# schematic.net
KiCad netlist of a schematic drawn in EAGLE
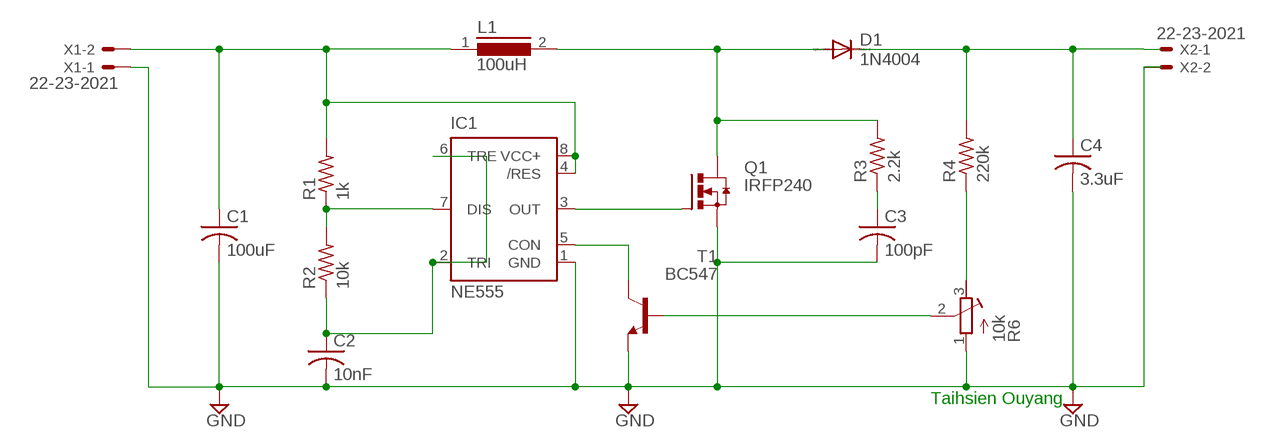
[diagram p0: schematic, sheet 1]

(export (version "E")
  (design (tool "Eeschema 10.0.6"))
  (components
    (comp (ref "C1")
      (value "100uF")
      (footprint "eagle-import:C050-025X075")
      (libsource (lib "eagle-import") (part "C-US050-025X075"))
    )
    (comp (ref "C2")
      (value "10nF")
      (footprint "eagle-import:C050-025X075")
      (libsource (lib "eagle-import") (part "C-US050-025X075"))
    )
    (comp (ref "C3")
      (value "100pF")
      (footprint "eagle-import:C050-025X075")
      (libsource (lib "eagle-import") (part "C-US050-025X075"))
    )
    (comp (ref "C4")
      (value "3.3uF")
      (footprint "eagle-import:C050-025X075")
      (libsource (lib "eagle-import") (part "C-US050-025X075"))
    )
    (comp (ref "D1")
      (value "1N4004")
      (footprint "eagle-import:DO41-10")
      (libsource (lib "eagle-import") (part "1N4004"))
    )
    (comp (ref "IC1")
      (value "NE555")
      (footprint "eagle-import:DIL-08")
      (fields (field (name "MF") "Arrow Electronics") (field (name "MPN") "NE555N"))
      (libsource (lib "eagle-import") (part "NE555"))
    )
    (comp (ref "L1")
      (value "100uH")
      (footprint "eagle-import:SFT1040")
      (libsource (lib "eagle-import") (part "SFT1040"))
    )
    (comp (ref "Q1")
      (value "IRFP240")
      (footprint "eagle-import:TO247BV")
      (libsource (lib "eagle-import") (part "IRFP240"))
    )
    (comp (ref "R1")
      (value "1k")
      (footprint "eagle-import:0207_7")
      (libsource (lib "eagle-import") (part "R-US_0207/7"))
    )
    (comp (ref "R2")
      (value "10k")
      (footprint "eagle-import:0207_7")
      (libsource (lib "eagle-import") (part "R-US_0207/7"))
    )
    (comp (ref "R3")
      (value "2.2k")
      (footprint "eagle-import:0207_7")
      (libsource (lib "eagle-import") (part "R-US_0207/7"))
    )
    (comp (ref "R4")
      (value "220k")
      (footprint "eagle-import:0207_7")
      (libsource (lib "eagle-import") (part "R-US_0207/7"))
    )
    (comp (ref "R6")
      (value "10k")
      (footprint "eagle-import:RTRIM3339P")
      (libsource (lib "eagle-import") (part "R-TRIMM3339P"))
    )
    (comp (ref "T1")
      (value "BC547")
      (footprint "eagle-import:TO92")
      (libsource (lib "eagle-import") (part "BC547"))
    )
    (comp (ref "X1")
      (value "22-23-2021")
      (footprint "eagle-import:22-23-2021")
      (fields (field (name "MF") "MOLEX"))
      (libsource (lib "eagle-import") (part "22-23-2021"))
    )
    (comp (ref "X2")
      (value "22-23-2021")
      (footprint "eagle-import:22-23-2021")
      (fields (field (name "MF") "MOLEX"))
      (libsource (lib "eagle-import") (part "22-23-2021"))
    )
  )
  (nets
    (net (code "1") (name "GND") (class "Default")
      (node (ref "C1") (pin "2") (pinfunction "2_2") (pintype "passive"))
      (node (ref "C2") (pin "2") (pinfunction "2_2") (pintype "passive"))
      (node (ref "C3") (pin "2") (pinfunction "2_2") (pintype "passive"))
      (node (ref "C4") (pin "2") (pinfunction "2_2") (pintype "passive"))
      (node (ref "IC1") (pin "1") (pinfunction "GND_1") (pintype "power_in"))
      (node (ref "Q1") (pin "S") (pinfunction "S_S") (pintype "passive"))
      (node (ref "R6") (pin "1") (pinfunction "A_1") (pintype "passive"))
      (node (ref "T1") (pin "1") (pinfunction "E_1") (pintype "passive"))
      (node (ref "X1") (pin "1") (pinfunction "S_1") (pintype "passive"))
      (node (ref "X2") (pin "2") (pinfunction "S_2") (pintype "passive"))
    )
    (net (code "2") (name "Net-(C3-Pad1)") (class "Default")
      (node (ref "C3") (pin "1") (pinfunction "1_1") (pintype "passive"))
      (node (ref "R3") (pin "1") (pinfunction "1_1") (pintype "passive"))
    )
    (net (code "3") (name "Net-(D1-PadA)") (class "Default")
      (node (ref "D1") (pin "A") (pinfunction "A_A") (pintype "passive"))
      (node (ref "L1") (pin "2") (pinfunction "2_2") (pintype "passive"))
      (node (ref "Q1") (pin "D") (pinfunction "D_D") (pintype "passive"))
      (node (ref "R3") (pin "2") (pinfunction "2_2") (pintype "passive"))
    )
    (net (code "4") (name "Net-(IC1-CON)") (class "Default")
      (node (ref "IC1") (pin "5") (pinfunction "CON_5") (pintype "input"))
      (node (ref "T1") (pin "3") (pinfunction "C_3") (pintype "passive"))
    )
    (net (code "5") (name "Net-(IC1-DIS)") (class "Default")
      (node (ref "IC1") (pin "7") (pinfunction "DIS_7") (pintype "input"))
      (node (ref "R1") (pin "1") (pinfunction "1_1") (pintype "passive"))
      (node (ref "R2") (pin "2") (pinfunction "2_2") (pintype "passive"))
    )
    (net (code "6") (name "Net-(IC1-OUT)") (class "Default")
      (node (ref "IC1") (pin "3") (pinfunction "OUT_3") (pintype "output"))
      (node (ref "Q1") (pin "G") (pinfunction "G_G") (pintype "passive"))
    )
    (net (code "7") (name "Net-(IC1-TRE)") (class "Default")
      (node (ref "C2") (pin "1") (pinfunction "1_1") (pintype "passive"))
      (node (ref "IC1") (pin "2") (pinfunction "TRI_2") (pintype "input"))
      (node (ref "IC1") (pin "6") (pinfunction "TRE_6") (pintype "input"))
      (node (ref "R2") (pin "1") (pinfunction "1_1") (pintype "passive"))
    )
    (net (code "8") (name "Net-(IC1-VCC+)") (class "Default")
      (node (ref "C1") (pin "1") (pinfunction "1_1") (pintype "passive"))
      (node (ref "IC1") (pin "4") (pinfunction "/RES_4") (pintype "input"))
      (node (ref "IC1") (pin "8") (pinfunction "VCC+_8") (pintype "power_in"))
      (node (ref "L1") (pin "1") (pinfunction "1_1") (pintype "passive"))
      (node (ref "R1") (pin "2") (pinfunction "2_2") (pintype "passive"))
      (node (ref "X1") (pin "2") (pinfunction "S_2") (pintype "passive"))
    )
    (net (code "9") (name "Net-(R6-E)") (class "Default")
      (node (ref "R4") (pin "1") (pinfunction "1_1") (pintype "passive"))
      (node (ref "R6") (pin "3") (pinfunction "E_3") (pintype "passive"))
    )
    (net (code "10") (name "Net-(R6-S)") (class "Default")
      (node (ref "R6") (pin "2") (pinfunction "S_2") (pintype "passive"))
      (node (ref "T1") (pin "2") (pinfunction "B_2") (pintype "passive"))
    )
    (net (code "11") (name "Net-(X2A-S)") (class "Default")
      (node (ref "C4") (pin "1") (pinfunction "1_1") (pintype "passive"))
      (node (ref "D1") (pin "C") (pinfunction "C_C") (pintype "passive"))
      (node (ref "R4") (pin "2") (pinfunction "2_2") (pintype "passive"))
      (node (ref "X2") (pin "1") (pinfunction "S_1") (pintype "passive"))
    )
  )
)
